# smoothieboard-5driver_3.net
KiCad netlist of a schematic drawn in Altium Designer
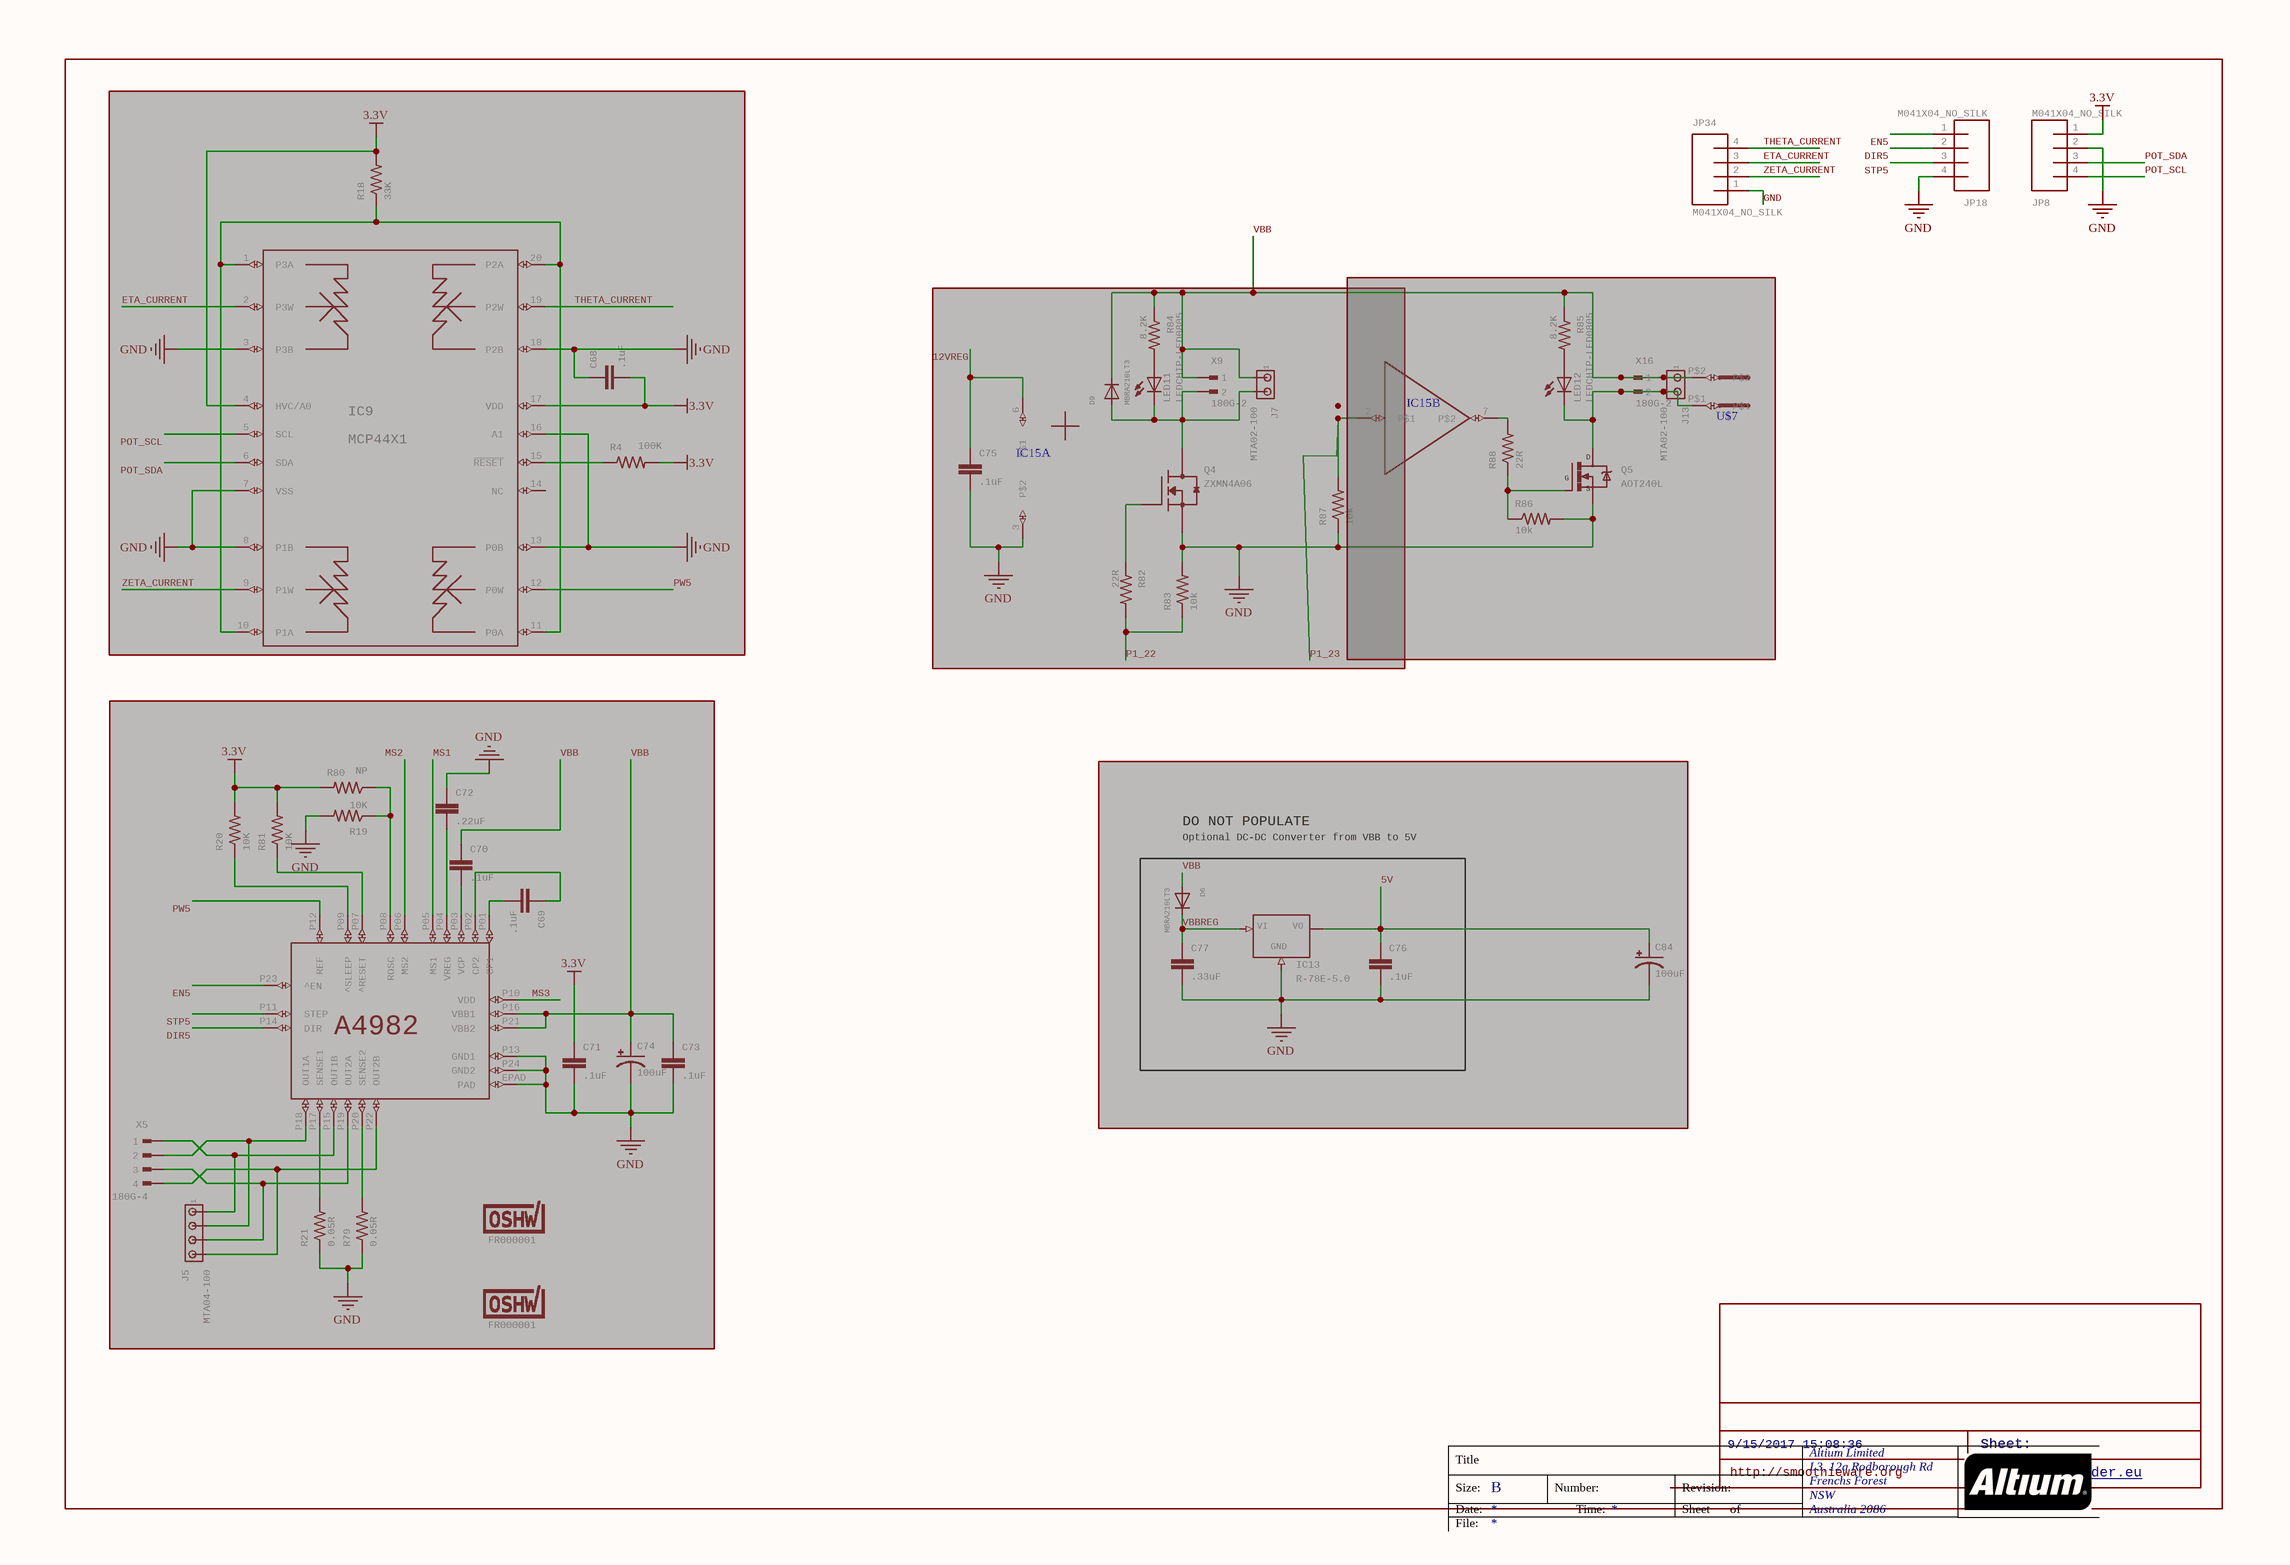
[diagram p0: smoothieboard-5driver_3.SchDoc]

(export (version "E")
  (design (tool "Eeschema 10.0.6"))
  (components
    (comp (ref "C68")
      (value ".1uF")
      (footprint "C0603")
      (description "CAPACITOR, European symbol")
      (libsource (lib "") (part "C-EUC0603_2"))
    )
    (comp (ref "C69")
      (value ".1uF")
      (footprint "C0603")
      (description "CAPACITOR, European symbol")
      (libsource (lib "rcl") (part "C-EUC0603"))
    )
    (comp (ref "C70")
      (value ".1uF")
      (footprint "C0603")
      (description "CAPACITOR, European symbol")
      (libsource (lib "") (part "C-EUC0603_1"))
    )
    (comp (ref "C71")
      (value ".1uF")
      (footprint "C0603")
      (description "CAPACITOR, European symbol")
      (libsource (lib "") (part "C-EUC0603_1"))
    )
    (comp (ref "C72")
      (value ".22uF")
      (footprint "C0603")
      (description "CAPACITOR, European symbol")
      (libsource (lib "") (part "C-EUC0603_1"))
    )
    (comp (ref "C73")
      (value ".1uF")
      (footprint "C0603")
      (description "CAPACITOR, European symbol")
      (libsource (lib "") (part "C-EUC0603_1"))
    )
    (comp (ref "C74")
      (value "100uF")
      (footprint "PANASONIC_E")
      (libsource (lib "SparkFun") (part "CAP_POLE"))
    )
    (comp (ref "C75")
      (value ".1uF")
      (footprint "C0603")
      (description "CAPACITOR, European symbol")
      (libsource (lib "resistor") (part "C-EUC0603"))
    )
    (comp (ref "C76")
      (value ".1uF")
      (footprint "C0603")
      (description "CAPACITOR, European symbol")
      (libsource (lib "") (part "C-EUC0603_1"))
    )
    (comp (ref "C77")
      (value ".33uF")
      (footprint "C0603")
      (description "CAPACITOR, European symbol")
      (libsource (lib "") (part "C-EUC0603_1"))
    )
    (comp (ref "C84")
      (value "100uF")
      (footprint "PANASONIC_D")
      (libsource (lib "SparkFun-Capacitors") (part "CAP_POLD"))
    )
    (comp (ref "D6")
      (value "MBRA210LT3")
      (footprint "SMADIODE")
      (libsource (lib "microbuilder") (part "DIODESMA"))
    )
    (comp (ref "D9")
      (value "MBRA210LT3")
      (footprint "SMADIODE")
      (libsource (lib "microbuilder") (part "DIODESMA"))
    )
    (comp (ref "IC9")
      (value "MCP44X1")
      (footprint "TSSOP20")
      (fields (field (name "LIBRARYNAME") "Geos"))
      (libsource (lib "Geos") (part "MCP44X1"))
    )
    (comp (ref "IC12")
      (value "A5984")
      (footprint "ETSSOP24")
      (fields (field (name "A4982") "A4982"))
      (libsource (lib "A4982") (part "A4982"))
    )
    (comp (ref "IC13")
      (value "R-78E-5.0")
      (footprint "R-78")
      (fields
        (field (name "GND") "GND")
        (field (name "VI") "VI")
        (field (name "VO") "VO")
        (field (name "LIBRARYNAME") "logxen")
      )
      (libsource (lib "logxen") (part "R-78"))
    )
    (comp (ref "IC15")
      (value "TC4427")
      (footprint "SOIC8")
      (fields (field (name "LIBRARYNAME") "custom_esorensen"))
      (libsource (lib "custom_esorensen") (part "TC4427"))
    )
    (comp (ref "J5")
      (value "MTA04-100")
      (footprint "10X04MTA")
      (description "AMP connector")
      (fields (field (name "1") "1"))
      (libsource (lib "con-amp") (part "MTA04-100"))
    )
    (comp (ref "J7")
      (value "MTA02-100")
      (footprint "10X02MTA")
      (description "AMP connector")
      (fields (field (name "1") "1"))
      (libsource (lib "con-amp") (part "MTA02-100"))
    )
    (comp (ref "J13")
      (value "MTA02-100")
      (footprint "10X02MTA")
      (description "AMP connector")
      (fields (field (name "1") "1"))
      (libsource (lib "con-amp") (part "MTA02-100"))
    )
    (comp (ref "JP8")
      (value "M041X04_NO_SILK")
      (footprint "1X04_NO_SILK")
      (libsource (lib "SparkFun") (part "M041X04_NO_SILK"))
    )
    (comp (ref "JP18")
      (value "M041X04_NO_SILK")
      (footprint "1X04_NO_SILK")
      (libsource (lib "SparkFun") (part "M041X04_NO_SILK"))
    )
    (comp (ref "JP34")
      (value "M041X04_NO_SILK")
      (footprint "1X04_NO_SILK")
      (libsource (lib "SparkFun") (part "M041X04_NO_SILK"))
    )
    (comp (ref "LED11")
      (value "LEDCHIP-LED0805")
      (footprint "CHIP-LED0805")
      (libsource (lib "led") (part "LEDCHIP-LED0805"))
    )
    (comp (ref "LED12")
      (value "LEDCHIP-LED0805")
      (footprint "CHIP-LED0805")
      (libsource (lib "led") (part "LEDCHIP-LED0805"))
    )
    (comp (ref "Q4")
      (value "ZXMN4A06")
      (footprint "SOT230P700X160-4N")
      (fields (field (name "LIBRARYNAME") "ipc-7351-transistor"))
      (libsource (lib "ipc-7351-transistor") (part "MOSFET-NCH_SOT-223"))
    )
    (comp (ref "Q5")
      (value "AOT240L")
      (footprint "TO220BV")
      (description "HEXFET Power MOSFET")
      (fields (field (name "D") "D") (field (name "S") "S") (field (name "G") "G"))
      (libsource (lib "transistor-power") (part "IRF540"))
    )
    (comp (ref "R4")
      (value "100K")
      (footprint "R0603")
      (description "RESISTOR, American symbol")
      (libsource (lib "resistor") (part "R-US_R0603"))
    )
    (comp (ref "R18")
      (value "33K")
      (footprint "R0603")
      (description "RESISTOR, American symbol")
      (libsource (lib "resistor") (part "R-US_R0603"))
    )
    (comp (ref "R19")
      (value "10K")
      (footprint "R0603")
      (description "RESISTOR, American symbol")
      (libsource (lib "resistor") (part "R-US_R0603"))
    )
    (comp (ref "R20")
      (value "10K")
      (footprint "R0603")
      (description "RESISTOR, American symbol")
      (libsource (lib "resistor") (part "R-US_R0603"))
    )
    (comp (ref "R21") (value "0.05R") (footprint "R2512") (libsource (lib "SparkFun") (part "RESISTOR2512")))
    (comp (ref "R79") (value "0.05R") (footprint "R2512") (libsource (lib "SparkFun") (part "RESISTOR2512")))
    (comp (ref "R80")
      (value "NP")
      (footprint "R0603")
      (description "RESISTOR, American symbol")
      (libsource (lib "resistor") (part "R-US_R0603"))
    )
    (comp (ref "R81")
      (value "10K")
      (footprint "R0603")
      (description "RESISTOR, American symbol")
      (libsource (lib "resistor") (part "R-US_R0603"))
    )
    (comp (ref "R82")
      (value "22R")
      (footprint "R0603")
      (description "RESISTOR, American symbol")
      (libsource (lib "resistor") (part "R-US_R0603"))
    )
    (comp (ref "R83")
      (value "10k")
      (footprint "R0603")
      (description "RESISTOR, American symbol")
      (libsource (lib "resistor") (part "R-US_R0603"))
    )
    (comp (ref "R84")
      (value "8.2K")
      (footprint "R0603")
      (description "RESISTOR, American symbol")
      (libsource (lib "resistor") (part "R-US_R0603"))
    )
    (comp (ref "R85")
      (value "8.2K")
      (footprint "R0603")
      (description "RESISTOR, American symbol")
      (libsource (lib "resistor") (part "R-US_R0603"))
    )
    (comp (ref "R86")
      (value "10k")
      (footprint "R0603")
      (description "RESISTOR, American symbol")
      (libsource (lib "resistor") (part "R-US_R0603"))
    )
    (comp (ref "R87")
      (value "10k")
      (footprint "R0603")
      (description "RESISTOR, American symbol")
      (libsource (lib "resistor") (part "R-US_R0603"))
    )
    (comp (ref "R88")
      (value "22R")
      (footprint "R0603")
      (description "RESISTOR, American symbol")
      (libsource (lib "resistor") (part "R-US_R0603"))
    )
    (comp (ref "U$7")
      (value "5MMCONN")
      (footprint "1715250000")
      (fields (field (name "LIBRARYNAME") "eric_sorensen"))
      (libsource (lib "eric_sorensen") (part "5MMCONN"))
    )
    (comp (ref "U$11")
      (value "FR000001")
      (footprint "CERT-SMALL-SILK")
      (fields (field (name "LIBRARYNAME") "OSHWA"))
      (libsource (lib "OSHWA") (part "CERT-SMALL"))
    )
    (comp (ref "U$12")
      (value "FR000001")
      (footprint "CERT-MED-SILK")
      (fields (field (name "LIBRARYNAME") "OSHWA"))
      (libsource (lib "OSHWA") (part "CERT-MEDIUM"))
    )
    (comp (ref "X5")
      (value "180G-4")
      (footprint "180G-4")
      (description "WEIDMUELLER CLAMP CONNECTOR")
      (fields (field (name "MF") "MF") (field (name "MPN") "MPN"))
      (libsource (lib "con-weidmueller-sl35") (part "180G-4"))
    )
    (comp (ref "X9")
      (value "180G-2")
      (footprint "180G-2")
      (description "WEIDMUELLER CLAMP CONNECTOR")
      (fields (field (name "MF") "MF") (field (name "MPN") "MPN"))
      (libsource (lib "con-weidmueller-sl35") (part "180G-2"))
    )
    (comp (ref "X16")
      (value "180G-2")
      (footprint "180G-2")
      (description "WEIDMUELLER CLAMP CONNECTOR")
      (fields (field (name "MF") "MF") (field (name "MPN") "MPN"))
      (libsource (lib "con-weidmueller-sl35") (part "180G-2"))
    )
  )
  (nets
    (net (code "1") (name "/5V") (class "Default")
      (node (ref "C76") (pin "1") (pinfunction "1_1") (pintype "passive"))
      (node (ref "C84") (pin "+") (pinfunction "+_+") (pintype "passive"))
      (node (ref "IC13") (pin "3") (pinfunction "VO_3") (pintype "bidirectional"))
    )
    (net (code "2") (name "/12VREG") (class "Default")
      (node (ref "C75") (pin "1") (pinfunction "1_1") (pintype "passive"))
      (node (ref "IC15") (pin "6") (pinfunction "P$1_6") (pintype "bidirectional"))
    )
    (net (code "3") (name "/DIR5") (class "Default")
      (node (ref "IC12") (pin "P14") (pinfunction "DIR_P14") (pintype "bidirectional"))
      (node (ref "JP18") (pin "2") (pinfunction "2_2") (pintype "passive"))
    )
    (net (code "4") (name "/EN5") (class "Default")
      (node (ref "IC12") (pin "P23") (pinfunction "^EN_P23") (pintype "bidirectional"))
      (node (ref "JP18") (pin "1") (pinfunction "1_1") (pintype "passive"))
    )
    (net (code "5") (name "/ETA_CURRENT") (class "Default")
      (node (ref "IC9") (pin "2") (pinfunction "P3W_2") (pintype "bidirectional"))
      (node (ref "JP34") (pin "3") (pinfunction "3_3") (pintype "passive"))
    )
    (net (code "6") (name "/MS1") (class "Default")
      (node (ref "IC12") (pin "P05") (pinfunction "MS1_P05") (pintype "bidirectional"))
    )
    (net (code "7") (name "/MS2") (class "Default")
      (node (ref "IC12") (pin "P06") (pinfunction "MS2_P06") (pintype "bidirectional"))
    )
    (net (code "8") (name "/MS3") (class "Default")
      (node (ref "IC12") (pin "P10") (pinfunction "VDD_P10") (pintype "bidirectional"))
    )
    (net (code "9") (name "/P1_22") (class "Default")
      (node (ref "R82") (pin "2") (pinfunction "2_2") (pintype "passive"))
      (node (ref "R83") (pin "1") (pinfunction "1_1") (pintype "passive"))
    )
    (net (code "10") (name "/P1_23") (class "Default")
      (node (ref "IC15") (pin "2") (pinfunction "P$1_2") (pintype "bidirectional"))
      (node (ref "R87") (pin "2") (pinfunction "2_2") (pintype "passive"))
    )
    (net (code "11") (name "/POT_SCL") (class "Default")
      (node (ref "IC9") (pin "5") (pinfunction "SCL_5") (pintype "bidirectional"))
      (node (ref "JP8") (pin "4") (pinfunction "4_4") (pintype "passive"))
    )
    (net (code "12") (name "/POT_SDA") (class "Default")
      (node (ref "IC9") (pin "6") (pinfunction "SDA_6") (pintype "bidirectional"))
      (node (ref "JP8") (pin "3") (pinfunction "3_3") (pintype "passive"))
    )
    (net (code "13") (name "/PW5") (class "Default")
      (node (ref "IC12") (pin "P12") (pinfunction "REF_P12") (pintype "bidirectional"))
      (node (ref "IC9") (pin "12") (pinfunction "P0W_12") (pintype "bidirectional"))
    )
    (net (code "14") (name "/STP5") (class "Default")
      (node (ref "IC12") (pin "P11") (pinfunction "STEP_P11") (pintype "bidirectional"))
      (node (ref "JP18") (pin "3") (pinfunction "3_3") (pintype "passive"))
    )
    (net (code "15") (name "/THETA_CURRENT") (class "Default")
      (node (ref "IC9") (pin "19") (pinfunction "P2W_19") (pintype "bidirectional"))
      (node (ref "JP34") (pin "4") (pinfunction "4_4") (pintype "passive"))
    )
    (net (code "16") (name "/VBB") (class "Default")
      (node (ref "C70") (pin "1") (pinfunction "1_1") (pintype "passive"))
      (node (ref "C73") (pin "1") (pinfunction "1_1") (pintype "passive"))
      (node (ref "C74") (pin "+") (pinfunction "+_+") (pintype "passive"))
      (node (ref "D6") (pin "A") (pinfunction "A_A") (pintype "passive"))
      (node (ref "D9") (pin "C") (pinfunction "C_C") (pintype "passive"))
      (node (ref "IC12") (pin "P16") (pinfunction "VBB1_P16") (pintype "bidirectional"))
      (node (ref "IC12") (pin "P21") (pinfunction "VBB2_P21") (pintype "bidirectional"))
      (node (ref "J13") (pin "1") (pinfunction "1_1") (pintype "passive"))
      (node (ref "J7") (pin "1") (pinfunction "1_1") (pintype "passive"))
      (node (ref "R84") (pin "1") (pinfunction "1_1") (pintype "passive"))
      (node (ref "R85") (pin "1") (pinfunction "1_1") (pintype "passive"))
      (node (ref "U$7") (pin "P$2") (pinfunction "P$2_P$2") (pintype "bidirectional"))
      (node (ref "X16") (pin "1") (pinfunction "1_1") (pintype "passive"))
      (node (ref "X9") (pin "1") (pinfunction "1_1") (pintype "passive"))
    )
    (net (code "17") (name "/VBBREG") (class "Default")
      (node (ref "C77") (pin "1") (pinfunction "1_1") (pintype "passive"))
      (node (ref "D6") (pin "C") (pinfunction "C_C") (pintype "passive"))
      (node (ref "IC13") (pin "1") (pinfunction "VI_1") (pintype "input"))
    )
    (net (code "18") (name "/ZETA_CURRENT") (class "Default")
      (node (ref "IC9") (pin "9") (pinfunction "P1W_9") (pintype "bidirectional"))
      (node (ref "JP34") (pin "2") (pinfunction "2_2") (pintype "passive"))
    )
    (net (code "19") (name "3.3V") (class "Default")
      (node (ref "C68") (pin "2") (pinfunction "2_2") (pintype "passive"))
      (node (ref "C71") (pin "1") (pinfunction "1_1") (pintype "passive"))
      (node (ref "IC9") (pin "17") (pinfunction "VDD_17") (pintype "bidirectional"))
      (node (ref "IC9") (pin "4") (pinfunction "HVC/A0_4") (pintype "bidirectional"))
      (node (ref "JP8") (pin "1") (pinfunction "1_1") (pintype "passive"))
      (node (ref "R18") (pin "2") (pinfunction "2_2") (pintype "passive"))
      (node (ref "R20") (pin "2") (pinfunction "2_2") (pintype "passive"))
      (node (ref "R4") (pin "2") (pinfunction "2_2") (pintype "passive"))
      (node (ref "R80") (pin "2") (pinfunction "2_2") (pintype "passive"))
      (node (ref "R81") (pin "2") (pinfunction "2_2") (pintype "passive"))
    )
    (net (code "20") (name "GND") (class "Default")
      (node (ref "C68") (pin "1") (pinfunction "1_1") (pintype "passive"))
      (node (ref "C71") (pin "2") (pinfunction "2_2") (pintype "passive"))
      (node (ref "C72") (pin "1") (pinfunction "1_1") (pintype "passive"))
      (node (ref "C73") (pin "2") (pinfunction "2_2") (pintype "passive"))
      (node (ref "C74") (pin "-") (pinfunction "-_-") (pintype "passive"))
      (node (ref "C75") (pin "2") (pinfunction "2_2") (pintype "passive"))
      (node (ref "C76") (pin "2") (pinfunction "2_2") (pintype "passive"))
      (node (ref "C77") (pin "2") (pinfunction "2_2") (pintype "passive"))
      (node (ref "C84") (pin "-") (pinfunction "-_-") (pintype "passive"))
      (node (ref "IC12") (pin "EPAD") (pinfunction "PAD_EPAD") (pintype "bidirectional"))
      (node (ref "IC12") (pin "P13") (pinfunction "GND1_P13") (pintype "bidirectional"))
      (node (ref "IC12") (pin "P24") (pinfunction "GND2_P24") (pintype "bidirectional"))
      (node (ref "IC13") (pin "2") (pinfunction "GND_2") (pintype "input"))
      (node (ref "IC15") (pin "3") (pinfunction "P$2_3") (pintype "bidirectional"))
      (node (ref "IC9") (pin "13") (pinfunction "P0B_13") (pintype "bidirectional"))
      (node (ref "IC9") (pin "16") (pinfunction "A1_16") (pintype "bidirectional"))
      (node (ref "IC9") (pin "18") (pinfunction "P2B_18") (pintype "bidirectional"))
      (node (ref "IC9") (pin "3") (pinfunction "P3B_3") (pintype "bidirectional"))
      (node (ref "IC9") (pin "7") (pinfunction "VSS_7") (pintype "bidirectional"))
      (node (ref "IC9") (pin "8") (pinfunction "P1B_8") (pintype "bidirectional"))
      (node (ref "JP18") (pin "4") (pinfunction "4_4") (pintype "passive"))
      (node (ref "JP34") (pin "1") (pinfunction "1_1") (pintype "passive"))
      (node (ref "JP8") (pin "2") (pinfunction "2_2") (pintype "passive"))
      (node (ref "Q4") (pin "3") (pinfunction "S_3") (pintype "passive"))
      (node (ref "Q5") (pin "S") (pinfunction "S_S") (pintype "passive"))
      (node (ref "R19") (pin "2") (pinfunction "2_2") (pintype "passive"))
      (node (ref "R21") (pin "1") (pinfunction "1_1") (pintype "passive"))
      (node (ref "R79") (pin "1") (pinfunction "1_1") (pintype "passive"))
      (node (ref "R83") (pin "2") (pinfunction "2_2") (pintype "passive"))
      (node (ref "R86") (pin "2") (pinfunction "2_2") (pintype "passive"))
      (node (ref "R87") (pin "1") (pinfunction "1_1") (pintype "passive"))
    )
    (net (code "21") (name "Net-(IC9-P0A)") (class "Default")
      (node (ref "IC9") (pin "1") (pinfunction "P3A_1") (pintype "bidirectional"))
      (node (ref "IC9") (pin "10") (pinfunction "P1A_10") (pintype "bidirectional"))
      (node (ref "IC9") (pin "11") (pinfunction "P0A_11") (pintype "bidirectional"))
      (node (ref "IC9") (pin "20") (pinfunction "P2A_20") (pintype "bidirectional"))
      (node (ref "R18") (pin "1") (pinfunction "1_1") (pintype "passive"))
    )
    (net (code "22") (name "Net-(IC9-~{RESET})") (class "Default")
      (node (ref "IC9") (pin "15") (pinfunction "~{RESET}_15") (pintype "bidirectional"))
      (node (ref "R4") (pin "1") (pinfunction "1_1") (pintype "passive"))
    )
    (net (code "23") (name "Net-(IC12-CP1)") (class "Default")
      (node (ref "C69") (pin "2") (pinfunction "2_2") (pintype "passive"))
      (node (ref "IC12") (pin "P01") (pinfunction "CP1_P01") (pintype "bidirectional"))
    )
    (net (code "24") (name "Net-(IC12-CP2)") (class "Default")
      (node (ref "C69") (pin "1") (pinfunction "1_1") (pintype "passive"))
      (node (ref "IC12") (pin "P02") (pinfunction "CP2_P02") (pintype "bidirectional"))
    )
    (net (code "25") (name "Net-(IC12-OUT1A)") (class "Default")
      (node (ref "IC12") (pin "P18") (pinfunction "OUT1A_P18") (pintype "bidirectional"))
      (node (ref "J5") (pin "2") (pinfunction "2_2") (pintype "passive"))
      (node (ref "X5") (pin "2") (pinfunction "2_2") (pintype "passive"))
    )
    (net (code "26") (name "Net-(IC12-OUT1B)") (class "Default")
      (node (ref "IC12") (pin "P15") (pinfunction "OUT1B_P15") (pintype "bidirectional"))
      (node (ref "J5") (pin "1") (pinfunction "1_1") (pintype "passive"))
      (node (ref "X5") (pin "1") (pinfunction "1_1") (pintype "passive"))
    )
    (net (code "27") (name "Net-(IC12-OUT2A)") (class "Default")
      (node (ref "IC12") (pin "P19") (pinfunction "OUT2A_P19") (pintype "bidirectional"))
      (node (ref "J5") (pin "3") (pinfunction "3_3") (pintype "passive"))
      (node (ref "X5") (pin "3") (pinfunction "3_3") (pintype "passive"))
    )
    (net (code "28") (name "Net-(IC12-OUT2B)") (class "Default")
      (node (ref "IC12") (pin "P22") (pinfunction "OUT2B_P22") (pintype "bidirectional"))
      (node (ref "J5") (pin "4") (pinfunction "4_4") (pintype "passive"))
      (node (ref "X5") (pin "4") (pinfunction "4_4") (pintype "passive"))
    )
    (net (code "29") (name "Net-(IC12-ROSC)") (class "Default")
      (node (ref "IC12") (pin "P08") (pinfunction "ROSC_P08") (pintype "bidirectional"))
      (node (ref "R19") (pin "1") (pinfunction "1_1") (pintype "passive"))
      (node (ref "R80") (pin "1") (pinfunction "1_1") (pintype "passive"))
    )
    (net (code "30") (name "Net-(IC12-SENSE1)") (class "Default")
      (node (ref "IC12") (pin "P17") (pinfunction "SENSE1_P17") (pintype "bidirectional"))
      (node (ref "R21") (pin "2") (pinfunction "2_2") (pintype "passive"))
    )
    (net (code "31") (name "Net-(IC12-SENSE2)") (class "Default")
      (node (ref "IC12") (pin "P20") (pinfunction "SENSE2_P20") (pintype "bidirectional"))
      (node (ref "R79") (pin "2") (pinfunction "2_2") (pintype "passive"))
    )
    (net (code "32") (name "Net-(IC12-VCP)") (class "Default")
      (node (ref "C70") (pin "2") (pinfunction "2_2") (pintype "passive"))
      (node (ref "IC12") (pin "P03") (pinfunction "VCP_P03") (pintype "bidirectional"))
    )
    (net (code "33") (name "Net-(IC12-VREG)") (class "Default")
      (node (ref "C72") (pin "2") (pinfunction "2_2") (pintype "passive"))
      (node (ref "IC12") (pin "P04") (pinfunction "VREG_P04") (pintype "bidirectional"))
    )
    (net (code "34") (name "Net-(IC12-^RESET)") (class "Default")
      (node (ref "IC12") (pin "P07") (pinfunction "^RESET_P07") (pintype "bidirectional"))
      (node (ref "R81") (pin "1") (pinfunction "1_1") (pintype "passive"))
    )
    (net (code "35") (name "Net-(IC12-^SLEEP)") (class "Default")
      (node (ref "IC12") (pin "P09") (pinfunction "^SLEEP_P09") (pintype "bidirectional"))
      (node (ref "R20") (pin "1") (pinfunction "1_1") (pintype "passive"))
    )
    (net (code "36") (name "Net-(IC15B-P$2)") (class "Default")
      (node (ref "IC15") (pin "7") (pinfunction "P$2_7") (pintype "bidirectional"))
      (node (ref "R88") (pin "2") (pinfunction "2_2") (pintype "passive"))
    )
    (net (code "37") (name "Net-(J13-Pad2)") (class "Default")
      (node (ref "J13") (pin "2") (pinfunction "2_2") (pintype "passive"))
      (node (ref "LED12") (pin "C") (pinfunction "C_C") (pintype "passive"))
      (node (ref "Q5") (pin "D") (pinfunction "D_D") (pintype "passive"))
      (node (ref "U$7") (pin "P$1") (pinfunction "P$1_P$1") (pintype "bidirectional"))
      (node (ref "X16") (pin "2") (pinfunction "2_2") (pintype "passive"))
    )
    (net (code "38") (name "Net-(LED11-PadA)") (class "Default")
      (node (ref "LED11") (pin "A") (pinfunction "A_A") (pintype "passive"))
      (node (ref "R84") (pin "2") (pinfunction "2_2") (pintype "passive"))
    )
    (net (code "39") (name "Net-(LED12-PadA)") (class "Default")
      (node (ref "LED12") (pin "A") (pinfunction "A_A") (pintype "passive"))
      (node (ref "R85") (pin "2") (pinfunction "2_2") (pintype "passive"))
    )
    (net (code "40") (name "Net-(Q4-D)") (class "Default")
      (node (ref "D9") (pin "A") (pinfunction "A_A") (pintype "passive"))
      (node (ref "J7") (pin "2") (pinfunction "2_2") (pintype "passive"))
      (node (ref "LED11") (pin "C") (pinfunction "C_C") (pintype "passive"))
      (node (ref "Q4") (pin "4") (pinfunction "D_4") (pintype "passive"))
      (node (ref "X9") (pin "2") (pinfunction "2_2") (pintype "passive"))
    )
    (net (code "41") (name "Net-(Q4-G)") (class "Default")
      (node (ref "Q4") (pin "1") (pinfunction "G_1") (pintype "passive"))
      (node (ref "R82") (pin "1") (pinfunction "1_1") (pintype "passive"))
    )
    (net (code "42") (name "Net-(Q5-PadG)") (class "Default")
      (node (ref "Q5") (pin "G") (pinfunction "G_G") (pintype "passive"))
      (node (ref "R86") (pin "1") (pinfunction "1_1") (pintype "passive"))
      (node (ref "R88") (pin "1") (pinfunction "1_1") (pintype "passive"))
    )
    (net (code "43") (name "unconnected-(IC9-NC-Pad14)") (class "Default")
      (node (ref "IC9") (pin "14") (pinfunction "NC_14") (pintype "bidirectional"))
    )
  )
)
